# LightTable_Borders_CurrentMirror.net
KiCad netlist of a schematic drawn in EAGLE
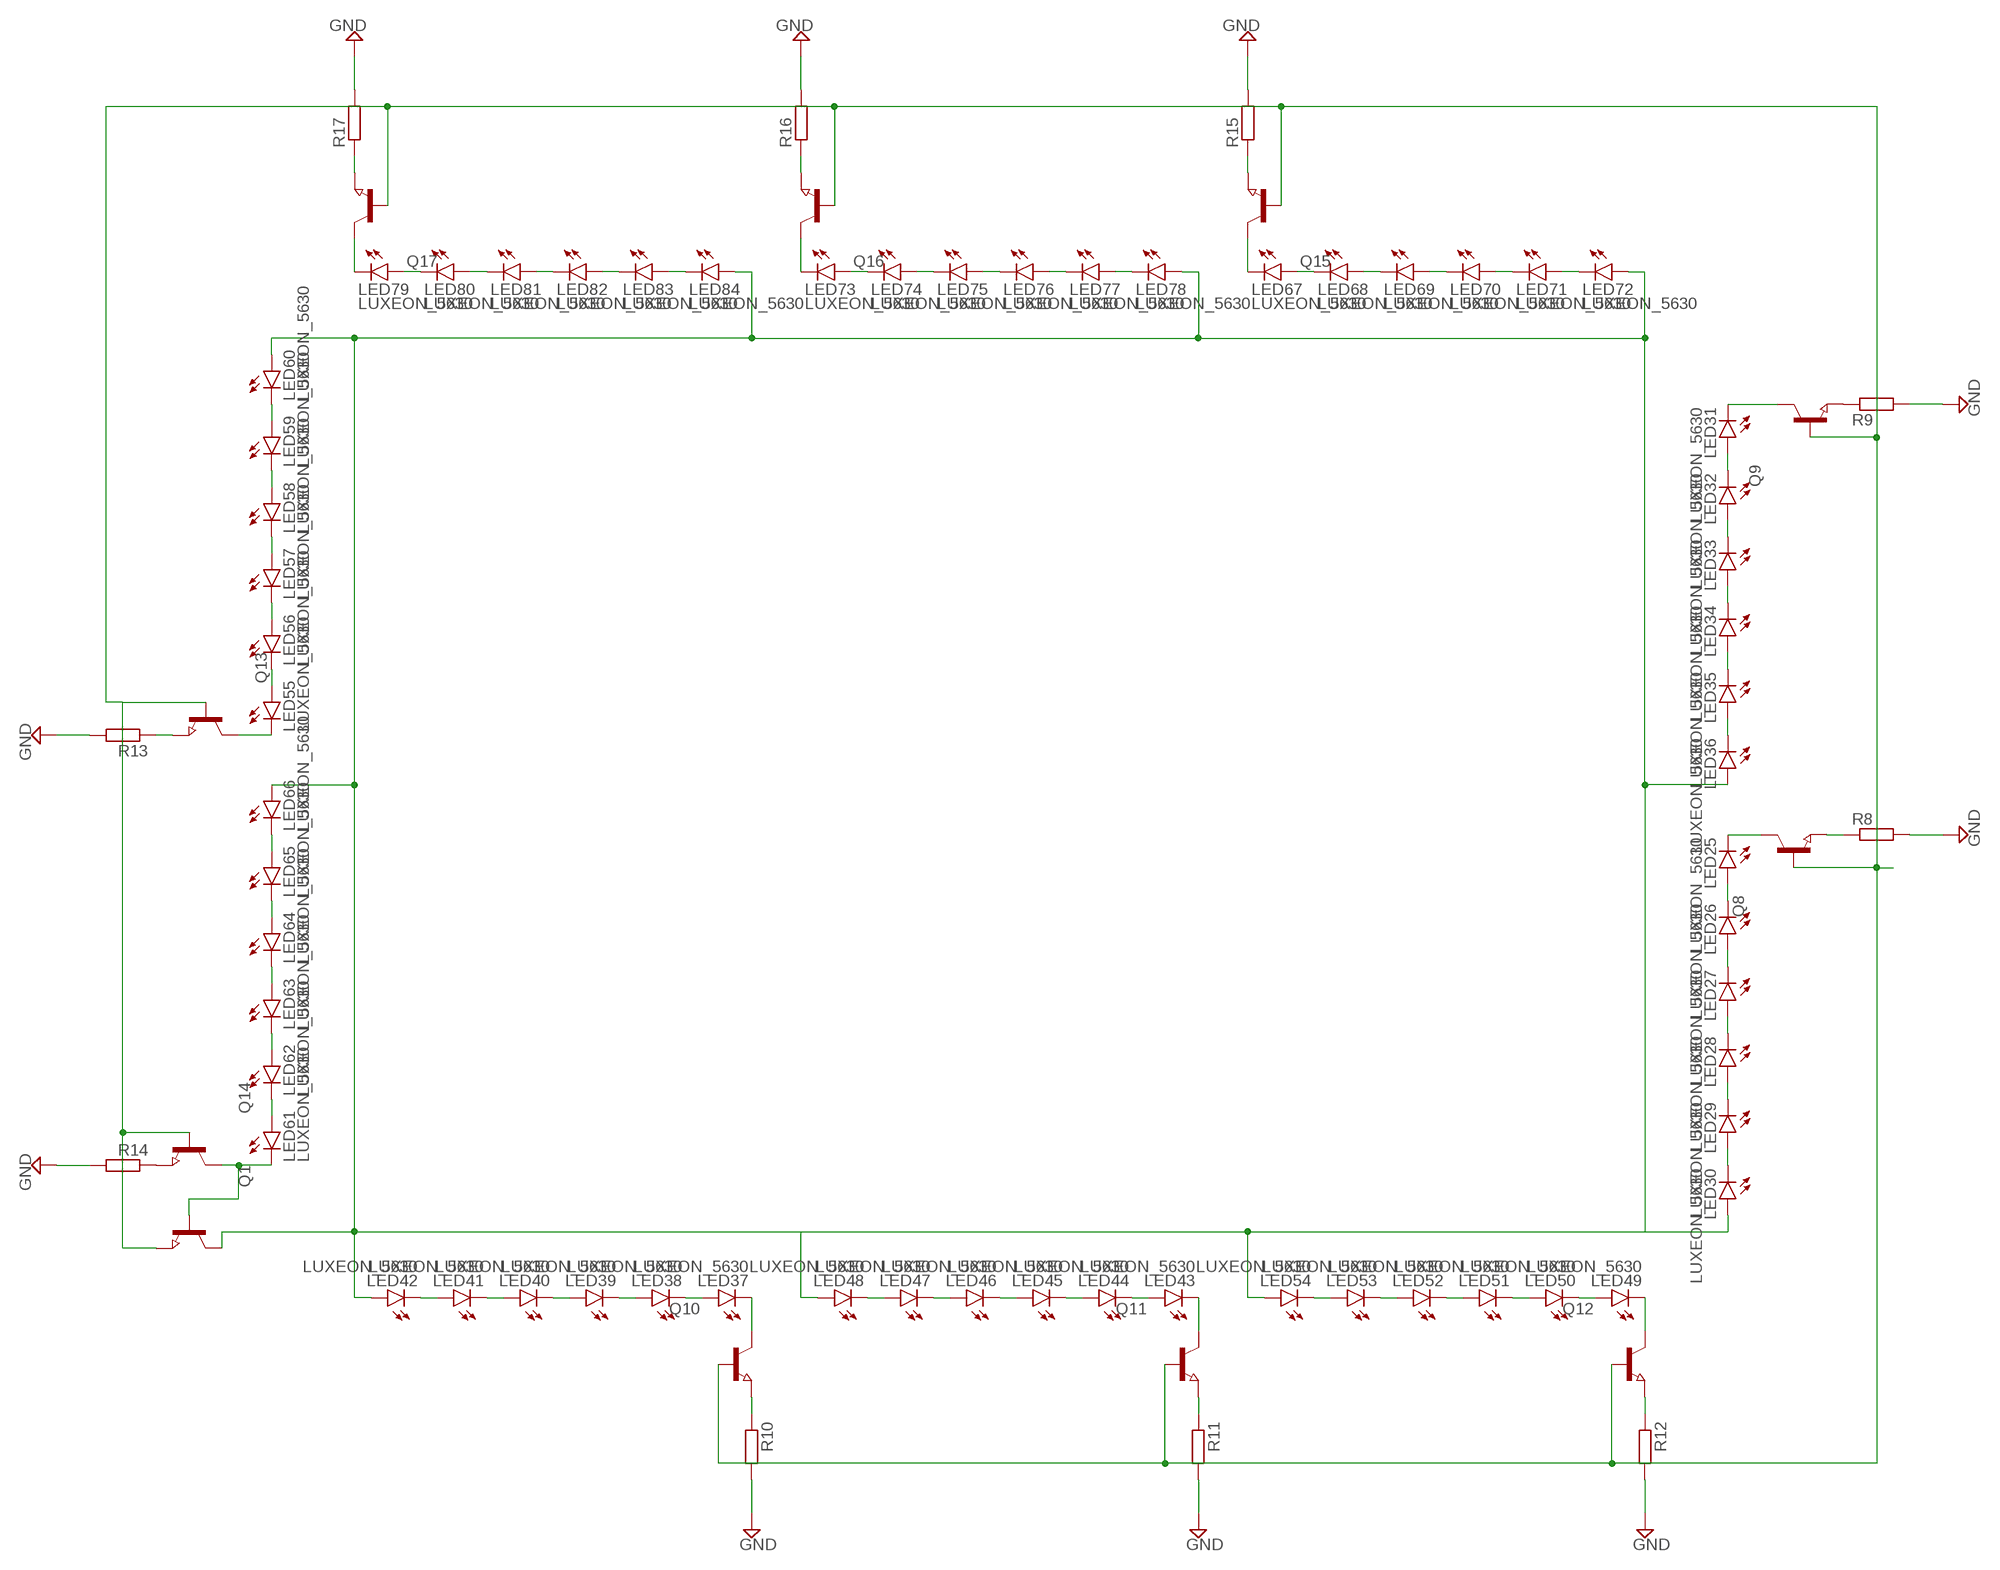
[diagram p0: schematic, sheet 1]

(export (version "E")
  (design (tool "Eeschema 10.0.6"))
  (components
    (comp (ref "LED25")
      (value "LUXEON_5630")
      (footprint "eagle-import:LUXEON_5630")
      (libsource (lib "eagle-import") (part "LUXEON_5630"))
    )
    (comp (ref "LED26")
      (value "LUXEON_5630")
      (footprint "eagle-import:LUXEON_5630")
      (libsource (lib "eagle-import") (part "LUXEON_5630"))
    )
    (comp (ref "LED27")
      (value "LUXEON_5630")
      (footprint "eagle-import:LUXEON_5630")
      (libsource (lib "eagle-import") (part "LUXEON_5630"))
    )
    (comp (ref "LED28")
      (value "LUXEON_5630")
      (footprint "eagle-import:LUXEON_5630")
      (libsource (lib "eagle-import") (part "LUXEON_5630"))
    )
    (comp (ref "LED29")
      (value "LUXEON_5630")
      (footprint "eagle-import:LUXEON_5630")
      (libsource (lib "eagle-import") (part "LUXEON_5630"))
    )
    (comp (ref "LED30")
      (value "LUXEON_5630")
      (footprint "eagle-import:LUXEON_5630")
      (libsource (lib "eagle-import") (part "LUXEON_5630"))
    )
    (comp (ref "LED31")
      (value "LUXEON_5630")
      (footprint "eagle-import:LUXEON_5630")
      (libsource (lib "eagle-import") (part "LUXEON_5630"))
    )
    (comp (ref "LED32")
      (value "LUXEON_5630")
      (footprint "eagle-import:LUXEON_5630")
      (libsource (lib "eagle-import") (part "LUXEON_5630"))
    )
    (comp (ref "LED33")
      (value "LUXEON_5630")
      (footprint "eagle-import:LUXEON_5630")
      (libsource (lib "eagle-import") (part "LUXEON_5630"))
    )
    (comp (ref "LED34")
      (value "LUXEON_5630")
      (footprint "eagle-import:LUXEON_5630")
      (libsource (lib "eagle-import") (part "LUXEON_5630"))
    )
    (comp (ref "LED35")
      (value "LUXEON_5630")
      (footprint "eagle-import:LUXEON_5630")
      (libsource (lib "eagle-import") (part "LUXEON_5630"))
    )
    (comp (ref "LED36")
      (value "LUXEON_5630")
      (footprint "eagle-import:LUXEON_5630")
      (libsource (lib "eagle-import") (part "LUXEON_5630"))
    )
    (comp (ref "LED37")
      (value "LUXEON_5630")
      (footprint "eagle-import:LUXEON_5630")
      (libsource (lib "eagle-import") (part "LUXEON_5630"))
    )
    (comp (ref "LED38")
      (value "LUXEON_5630")
      (footprint "eagle-import:LUXEON_5630")
      (libsource (lib "eagle-import") (part "LUXEON_5630"))
    )
    (comp (ref "LED39")
      (value "LUXEON_5630")
      (footprint "eagle-import:LUXEON_5630")
      (libsource (lib "eagle-import") (part "LUXEON_5630"))
    )
    (comp (ref "LED40")
      (value "LUXEON_5630")
      (footprint "eagle-import:LUXEON_5630")
      (libsource (lib "eagle-import") (part "LUXEON_5630"))
    )
    (comp (ref "LED41")
      (value "LUXEON_5630")
      (footprint "eagle-import:LUXEON_5630")
      (libsource (lib "eagle-import") (part "LUXEON_5630"))
    )
    (comp (ref "LED42")
      (value "LUXEON_5630")
      (footprint "eagle-import:LUXEON_5630")
      (libsource (lib "eagle-import") (part "LUXEON_5630"))
    )
    (comp (ref "LED43")
      (value "LUXEON_5630")
      (footprint "eagle-import:LUXEON_5630")
      (libsource (lib "eagle-import") (part "LUXEON_5630"))
    )
    (comp (ref "LED44")
      (value "LUXEON_5630")
      (footprint "eagle-import:LUXEON_5630")
      (libsource (lib "eagle-import") (part "LUXEON_5630"))
    )
    (comp (ref "LED45")
      (value "LUXEON_5630")
      (footprint "eagle-import:LUXEON_5630")
      (libsource (lib "eagle-import") (part "LUXEON_5630"))
    )
    (comp (ref "LED46")
      (value "LUXEON_5630")
      (footprint "eagle-import:LUXEON_5630")
      (libsource (lib "eagle-import") (part "LUXEON_5630"))
    )
    (comp (ref "LED47")
      (value "LUXEON_5630")
      (footprint "eagle-import:LUXEON_5630")
      (libsource (lib "eagle-import") (part "LUXEON_5630"))
    )
    (comp (ref "LED48")
      (value "LUXEON_5630")
      (footprint "eagle-import:LUXEON_5630")
      (libsource (lib "eagle-import") (part "LUXEON_5630"))
    )
    (comp (ref "LED49")
      (value "LUXEON_5630")
      (footprint "eagle-import:LUXEON_5630")
      (libsource (lib "eagle-import") (part "LUXEON_5630"))
    )
    (comp (ref "LED50")
      (value "LUXEON_5630")
      (footprint "eagle-import:LUXEON_5630")
      (libsource (lib "eagle-import") (part "LUXEON_5630"))
    )
    (comp (ref "LED51")
      (value "LUXEON_5630")
      (footprint "eagle-import:LUXEON_5630")
      (libsource (lib "eagle-import") (part "LUXEON_5630"))
    )
    (comp (ref "LED52")
      (value "LUXEON_5630")
      (footprint "eagle-import:LUXEON_5630")
      (libsource (lib "eagle-import") (part "LUXEON_5630"))
    )
    (comp (ref "LED53")
      (value "LUXEON_5630")
      (footprint "eagle-import:LUXEON_5630")
      (libsource (lib "eagle-import") (part "LUXEON_5630"))
    )
    (comp (ref "LED54")
      (value "LUXEON_5630")
      (footprint "eagle-import:LUXEON_5630")
      (libsource (lib "eagle-import") (part "LUXEON_5630"))
    )
    (comp (ref "LED55")
      (value "LUXEON_5630")
      (footprint "eagle-import:LUXEON_5630")
      (libsource (lib "eagle-import") (part "LUXEON_5630"))
    )
    (comp (ref "LED56")
      (value "LUXEON_5630")
      (footprint "eagle-import:LUXEON_5630")
      (libsource (lib "eagle-import") (part "LUXEON_5630"))
    )
    (comp (ref "LED57")
      (value "LUXEON_5630")
      (footprint "eagle-import:LUXEON_5630")
      (libsource (lib "eagle-import") (part "LUXEON_5630"))
    )
    (comp (ref "LED58")
      (value "LUXEON_5630")
      (footprint "eagle-import:LUXEON_5630")
      (libsource (lib "eagle-import") (part "LUXEON_5630"))
    )
    (comp (ref "LED59")
      (value "LUXEON_5630")
      (footprint "eagle-import:LUXEON_5630")
      (libsource (lib "eagle-import") (part "LUXEON_5630"))
    )
    (comp (ref "LED60")
      (value "LUXEON_5630")
      (footprint "eagle-import:LUXEON_5630")
      (libsource (lib "eagle-import") (part "LUXEON_5630"))
    )
    (comp (ref "LED61")
      (value "LUXEON_5630")
      (footprint "eagle-import:LUXEON_5630")
      (libsource (lib "eagle-import") (part "LUXEON_5630"))
    )
    (comp (ref "LED62")
      (value "LUXEON_5630")
      (footprint "eagle-import:LUXEON_5630")
      (libsource (lib "eagle-import") (part "LUXEON_5630"))
    )
    (comp (ref "LED63")
      (value "LUXEON_5630")
      (footprint "eagle-import:LUXEON_5630")
      (libsource (lib "eagle-import") (part "LUXEON_5630"))
    )
    (comp (ref "LED64")
      (value "LUXEON_5630")
      (footprint "eagle-import:LUXEON_5630")
      (libsource (lib "eagle-import") (part "LUXEON_5630"))
    )
    (comp (ref "LED65")
      (value "LUXEON_5630")
      (footprint "eagle-import:LUXEON_5630")
      (libsource (lib "eagle-import") (part "LUXEON_5630"))
    )
    (comp (ref "LED66")
      (value "LUXEON_5630")
      (footprint "eagle-import:LUXEON_5630")
      (libsource (lib "eagle-import") (part "LUXEON_5630"))
    )
    (comp (ref "LED67")
      (value "LUXEON_5630")
      (footprint "eagle-import:LUXEON_5630")
      (libsource (lib "eagle-import") (part "LUXEON_5630"))
    )
    (comp (ref "LED68")
      (value "LUXEON_5630")
      (footprint "eagle-import:LUXEON_5630")
      (libsource (lib "eagle-import") (part "LUXEON_5630"))
    )
    (comp (ref "LED69")
      (value "LUXEON_5630")
      (footprint "eagle-import:LUXEON_5630")
      (libsource (lib "eagle-import") (part "LUXEON_5630"))
    )
    (comp (ref "LED70")
      (value "LUXEON_5630")
      (footprint "eagle-import:LUXEON_5630")
      (libsource (lib "eagle-import") (part "LUXEON_5630"))
    )
    (comp (ref "LED71")
      (value "LUXEON_5630")
      (footprint "eagle-import:LUXEON_5630")
      (libsource (lib "eagle-import") (part "LUXEON_5630"))
    )
    (comp (ref "LED72")
      (value "LUXEON_5630")
      (footprint "eagle-import:LUXEON_5630")
      (libsource (lib "eagle-import") (part "LUXEON_5630"))
    )
    (comp (ref "LED73")
      (value "LUXEON_5630")
      (footprint "eagle-import:LUXEON_5630")
      (libsource (lib "eagle-import") (part "LUXEON_5630"))
    )
    (comp (ref "LED74")
      (value "LUXEON_5630")
      (footprint "eagle-import:LUXEON_5630")
      (libsource (lib "eagle-import") (part "LUXEON_5630"))
    )
    (comp (ref "LED75")
      (value "LUXEON_5630")
      (footprint "eagle-import:LUXEON_5630")
      (libsource (lib "eagle-import") (part "LUXEON_5630"))
    )
    (comp (ref "LED76")
      (value "LUXEON_5630")
      (footprint "eagle-import:LUXEON_5630")
      (libsource (lib "eagle-import") (part "LUXEON_5630"))
    )
    (comp (ref "LED77")
      (value "LUXEON_5630")
      (footprint "eagle-import:LUXEON_5630")
      (libsource (lib "eagle-import") (part "LUXEON_5630"))
    )
    (comp (ref "LED78")
      (value "LUXEON_5630")
      (footprint "eagle-import:LUXEON_5630")
      (libsource (lib "eagle-import") (part "LUXEON_5630"))
    )
    (comp (ref "LED79")
      (value "LUXEON_5630")
      (footprint "eagle-import:LUXEON_5630")
      (libsource (lib "eagle-import") (part "LUXEON_5630"))
    )
    (comp (ref "LED80")
      (value "LUXEON_5630")
      (footprint "eagle-import:LUXEON_5630")
      (libsource (lib "eagle-import") (part "LUXEON_5630"))
    )
    (comp (ref "LED81")
      (value "LUXEON_5630")
      (footprint "eagle-import:LUXEON_5630")
      (libsource (lib "eagle-import") (part "LUXEON_5630"))
    )
    (comp (ref "LED82")
      (value "LUXEON_5630")
      (footprint "eagle-import:LUXEON_5630")
      (libsource (lib "eagle-import") (part "LUXEON_5630"))
    )
    (comp (ref "LED83")
      (value "LUXEON_5630")
      (footprint "eagle-import:LUXEON_5630")
      (libsource (lib "eagle-import") (part "LUXEON_5630"))
    )
    (comp (ref "LED84")
      (value "LUXEON_5630")
      (footprint "eagle-import:LUXEON_5630")
      (libsource (lib "eagle-import") (part "LUXEON_5630"))
    )
    (comp (ref "Q1")
      (value "NPN-TRANSISTOR_SOT23")
      (footprint "eagle-import:SOT23")
      (libsource (lib "eagle-import") (part "NPN-TRANSISTOR_SOT23"))
    )
    (comp (ref "Q8")
      (value "NPN-TRANSISTOR_SOT23")
      (footprint "eagle-import:SOT23")
      (libsource (lib "eagle-import") (part "NPN-TRANSISTOR_SOT23"))
    )
    (comp (ref "Q9")
      (value "NPN-TRANSISTOR_SOT23")
      (footprint "eagle-import:SOT23")
      (libsource (lib "eagle-import") (part "NPN-TRANSISTOR_SOT23"))
    )
    (comp (ref "Q10")
      (value "NPN-TRANSISTOR_SOT23")
      (footprint "eagle-import:SOT23")
      (libsource (lib "eagle-import") (part "NPN-TRANSISTOR_SOT23"))
    )
    (comp (ref "Q11")
      (value "NPN-TRANSISTOR_SOT23")
      (footprint "eagle-import:SOT23")
      (libsource (lib "eagle-import") (part "NPN-TRANSISTOR_SOT23"))
    )
    (comp (ref "Q12")
      (value "NPN-TRANSISTOR_SOT23")
      (footprint "eagle-import:SOT23")
      (libsource (lib "eagle-import") (part "NPN-TRANSISTOR_SOT23"))
    )
    (comp (ref "Q13")
      (value "NPN-TRANSISTOR_SOT23")
      (footprint "eagle-import:SOT23")
      (libsource (lib "eagle-import") (part "NPN-TRANSISTOR_SOT23"))
    )
    (comp (ref "Q14")
      (value "NPN-TRANSISTOR_SOT23")
      (footprint "eagle-import:SOT23")
      (libsource (lib "eagle-import") (part "NPN-TRANSISTOR_SOT23"))
    )
    (comp (ref "Q15")
      (value "NPN-TRANSISTOR_SOT23")
      (footprint "eagle-import:SOT23")
      (libsource (lib "eagle-import") (part "NPN-TRANSISTOR_SOT23"))
    )
    (comp (ref "Q16")
      (value "NPN-TRANSISTOR_SOT23")
      (footprint "eagle-import:SOT23")
      (libsource (lib "eagle-import") (part "NPN-TRANSISTOR_SOT23"))
    )
    (comp (ref "Q17")
      (value "NPN-TRANSISTOR_SOT23")
      (footprint "eagle-import:SOT23")
      (libsource (lib "eagle-import") (part "NPN-TRANSISTOR_SOT23"))
    )
    (comp (ref "R8")
      (value "R-EU_R0805")
      (footprint "eagle-import:R0805")
      (libsource (lib "eagle-import") (part "R-EU_R0805"))
    )
    (comp (ref "R9")
      (value "R-EU_R0805")
      (footprint "eagle-import:R0805")
      (libsource (lib "eagle-import") (part "R-EU_R0805"))
    )
    (comp (ref "R10")
      (value "R-EU_R0805")
      (footprint "eagle-import:R0805")
      (libsource (lib "eagle-import") (part "R-EU_R0805"))
    )
    (comp (ref "R11")
      (value "R-EU_R0805")
      (footprint "eagle-import:R0805")
      (libsource (lib "eagle-import") (part "R-EU_R0805"))
    )
    (comp (ref "R12")
      (value "R-EU_R0805")
      (footprint "eagle-import:R0805")
      (libsource (lib "eagle-import") (part "R-EU_R0805"))
    )
    (comp (ref "R13")
      (value "R-EU_R0805")
      (footprint "eagle-import:R0805")
      (libsource (lib "eagle-import") (part "R-EU_R0805"))
    )
    (comp (ref "R14")
      (value "R-EU_R0805")
      (footprint "eagle-import:R0805")
      (libsource (lib "eagle-import") (part "R-EU_R0805"))
    )
    (comp (ref "R15")
      (value "R-EU_R0805")
      (footprint "eagle-import:R0805")
      (libsource (lib "eagle-import") (part "R-EU_R0805"))
    )
    (comp (ref "R16")
      (value "R-EU_R0805")
      (footprint "eagle-import:R0805")
      (libsource (lib "eagle-import") (part "R-EU_R0805"))
    )
    (comp (ref "R17")
      (value "R-EU_R0805")
      (footprint "eagle-import:R0805")
      (libsource (lib "eagle-import") (part "R-EU_R0805"))
    )
  )
  (nets
    (net (code "1") (name "GND") (class "Default")
      (node (ref "R10") (pin "2") (pinfunction "2_2") (pintype "passive"))
      (node (ref "R11") (pin "2") (pinfunction "2_2") (pintype "passive"))
      (node (ref "R12") (pin "2") (pinfunction "2_2") (pintype "passive"))
      (node (ref "R13") (pin "2") (pinfunction "2_2") (pintype "passive"))
      (node (ref "R14") (pin "2") (pinfunction "2_2") (pintype "passive"))
      (node (ref "R15") (pin "2") (pinfunction "2_2") (pintype "passive"))
      (node (ref "R16") (pin "2") (pinfunction "2_2") (pintype "passive"))
      (node (ref "R17") (pin "2") (pinfunction "2_2") (pintype "passive"))
      (node (ref "R8") (pin "2") (pinfunction "2_2") (pintype "passive"))
      (node (ref "R9") (pin "2") (pinfunction "2_2") (pintype "passive"))
    )
    (net (code "2") (name "Net-(LED25-A)") (class "Default")
      (node (ref "LED25") (pin "2") (pinfunction "A_2") (pintype "passive"))
      (node (ref "LED26") (pin "1@1") (pinfunction "C_1@1") (pintype "passive"))
      (node (ref "LED26") (pin "1@2") (pinfunction "C_1@2") (pintype "passive"))
    )
    (net (code "3") (name "Net-(LED26-A)") (class "Default")
      (node (ref "LED26") (pin "2") (pinfunction "A_2") (pintype "passive"))
      (node (ref "LED27") (pin "1@1") (pinfunction "C_1@1") (pintype "passive"))
      (node (ref "LED27") (pin "1@2") (pinfunction "C_1@2") (pintype "passive"))
    )
    (net (code "4") (name "Net-(LED27-A)") (class "Default")
      (node (ref "LED27") (pin "2") (pinfunction "A_2") (pintype "passive"))
      (node (ref "LED28") (pin "1@1") (pinfunction "C_1@1") (pintype "passive"))
      (node (ref "LED28") (pin "1@2") (pinfunction "C_1@2") (pintype "passive"))
    )
    (net (code "5") (name "Net-(LED28-A)") (class "Default")
      (node (ref "LED28") (pin "2") (pinfunction "A_2") (pintype "passive"))
      (node (ref "LED29") (pin "1@1") (pinfunction "C_1@1") (pintype "passive"))
      (node (ref "LED29") (pin "1@2") (pinfunction "C_1@2") (pintype "passive"))
    )
    (net (code "6") (name "Net-(LED29-A)") (class "Default")
      (node (ref "LED29") (pin "2") (pinfunction "A_2") (pintype "passive"))
      (node (ref "LED30") (pin "1@1") (pinfunction "C_1@1") (pintype "passive"))
      (node (ref "LED30") (pin "1@2") (pinfunction "C_1@2") (pintype "passive"))
    )
    (net (code "7") (name "Net-(LED30-A)") (class "Default")
      (node (ref "LED30") (pin "2") (pinfunction "A_2") (pintype "passive"))
      (node (ref "LED36") (pin "2") (pinfunction "A_2") (pintype "passive"))
      (node (ref "LED42") (pin "2") (pinfunction "A_2") (pintype "passive"))
      (node (ref "LED48") (pin "2") (pinfunction "A_2") (pintype "passive"))
      (node (ref "LED54") (pin "2") (pinfunction "A_2") (pintype "passive"))
      (node (ref "LED60") (pin "2") (pinfunction "A_2") (pintype "passive"))
      (node (ref "LED66") (pin "2") (pinfunction "A_2") (pintype "passive"))
      (node (ref "LED72") (pin "2") (pinfunction "A_2") (pintype "passive"))
      (node (ref "LED78") (pin "2") (pinfunction "A_2") (pintype "passive"))
      (node (ref "LED84") (pin "2") (pinfunction "A_2") (pintype "passive"))
      (node (ref "Q1") (pin "3") (pinfunction "C_3") (pintype "passive"))
    )
    (net (code "8") (name "Net-(LED31-A)") (class "Default")
      (node (ref "LED31") (pin "2") (pinfunction "A_2") (pintype "passive"))
      (node (ref "LED32") (pin "1@1") (pinfunction "C_1@1") (pintype "passive"))
      (node (ref "LED32") (pin "1@2") (pinfunction "C_1@2") (pintype "passive"))
    )
    (net (code "9") (name "Net-(LED32-A)") (class "Default")
      (node (ref "LED32") (pin "2") (pinfunction "A_2") (pintype "passive"))
      (node (ref "LED33") (pin "1@1") (pinfunction "C_1@1") (pintype "passive"))
      (node (ref "LED33") (pin "1@2") (pinfunction "C_1@2") (pintype "passive"))
    )
    (net (code "10") (name "Net-(LED33-A)") (class "Default")
      (node (ref "LED33") (pin "2") (pinfunction "A_2") (pintype "passive"))
      (node (ref "LED34") (pin "1@1") (pinfunction "C_1@1") (pintype "passive"))
      (node (ref "LED34") (pin "1@2") (pinfunction "C_1@2") (pintype "passive"))
    )
    (net (code "11") (name "Net-(LED34-A)") (class "Default")
      (node (ref "LED34") (pin "2") (pinfunction "A_2") (pintype "passive"))
      (node (ref "LED35") (pin "1@1") (pinfunction "C_1@1") (pintype "passive"))
      (node (ref "LED35") (pin "1@2") (pinfunction "C_1@2") (pintype "passive"))
    )
    (net (code "12") (name "Net-(LED35-A)") (class "Default")
      (node (ref "LED35") (pin "2") (pinfunction "A_2") (pintype "passive"))
      (node (ref "LED36") (pin "1@1") (pinfunction "C_1@1") (pintype "passive"))
      (node (ref "LED36") (pin "1@2") (pinfunction "C_1@2") (pintype "passive"))
    )
    (net (code "13") (name "Net-(LED37-A)") (class "Default")
      (node (ref "LED37") (pin "2") (pinfunction "A_2") (pintype "passive"))
      (node (ref "LED38") (pin "1@1") (pinfunction "C_1@1") (pintype "passive"))
      (node (ref "LED38") (pin "1@2") (pinfunction "C_1@2") (pintype "passive"))
    )
    (net (code "14") (name "Net-(LED38-A)") (class "Default")
      (node (ref "LED38") (pin "2") (pinfunction "A_2") (pintype "passive"))
      (node (ref "LED39") (pin "1@1") (pinfunction "C_1@1") (pintype "passive"))
      (node (ref "LED39") (pin "1@2") (pinfunction "C_1@2") (pintype "passive"))
    )
    (net (code "15") (name "Net-(LED39-A)") (class "Default")
      (node (ref "LED39") (pin "2") (pinfunction "A_2") (pintype "passive"))
      (node (ref "LED40") (pin "1@1") (pinfunction "C_1@1") (pintype "passive"))
      (node (ref "LED40") (pin "1@2") (pinfunction "C_1@2") (pintype "passive"))
    )
    (net (code "16") (name "Net-(LED40-A)") (class "Default")
      (node (ref "LED40") (pin "2") (pinfunction "A_2") (pintype "passive"))
      (node (ref "LED41") (pin "1@1") (pinfunction "C_1@1") (pintype "passive"))
      (node (ref "LED41") (pin "1@2") (pinfunction "C_1@2") (pintype "passive"))
    )
    (net (code "17") (name "Net-(LED41-A)") (class "Default")
      (node (ref "LED41") (pin "2") (pinfunction "A_2") (pintype "passive"))
      (node (ref "LED42") (pin "1@1") (pinfunction "C_1@1") (pintype "passive"))
      (node (ref "LED42") (pin "1@2") (pinfunction "C_1@2") (pintype "passive"))
    )
    (net (code "18") (name "Net-(LED43-A)") (class "Default")
      (node (ref "LED43") (pin "2") (pinfunction "A_2") (pintype "passive"))
      (node (ref "LED44") (pin "1@1") (pinfunction "C_1@1") (pintype "passive"))
      (node (ref "LED44") (pin "1@2") (pinfunction "C_1@2") (pintype "passive"))
    )
    (net (code "19") (name "Net-(LED44-A)") (class "Default")
      (node (ref "LED44") (pin "2") (pinfunction "A_2") (pintype "passive"))
      (node (ref "LED45") (pin "1@1") (pinfunction "C_1@1") (pintype "passive"))
      (node (ref "LED45") (pin "1@2") (pinfunction "C_1@2") (pintype "passive"))
    )
    (net (code "20") (name "Net-(LED45-A)") (class "Default")
      (node (ref "LED45") (pin "2") (pinfunction "A_2") (pintype "passive"))
      (node (ref "LED46") (pin "1@1") (pinfunction "C_1@1") (pintype "passive"))
      (node (ref "LED46") (pin "1@2") (pinfunction "C_1@2") (pintype "passive"))
    )
    (net (code "21") (name "Net-(LED46-A)") (class "Default")
      (node (ref "LED46") (pin "2") (pinfunction "A_2") (pintype "passive"))
      (node (ref "LED47") (pin "1@1") (pinfunction "C_1@1") (pintype "passive"))
      (node (ref "LED47") (pin "1@2") (pinfunction "C_1@2") (pintype "passive"))
    )
    (net (code "22") (name "Net-(LED47-A)") (class "Default")
      (node (ref "LED47") (pin "2") (pinfunction "A_2") (pintype "passive"))
      (node (ref "LED48") (pin "1@1") (pinfunction "C_1@1") (pintype "passive"))
      (node (ref "LED48") (pin "1@2") (pinfunction "C_1@2") (pintype "passive"))
    )
    (net (code "23") (name "Net-(LED49-A)") (class "Default")
      (node (ref "LED49") (pin "2") (pinfunction "A_2") (pintype "passive"))
      (node (ref "LED50") (pin "1@1") (pinfunction "C_1@1") (pintype "passive"))
      (node (ref "LED50") (pin "1@2") (pinfunction "C_1@2") (pintype "passive"))
    )
    (net (code "24") (name "Net-(LED50-A)") (class "Default")
      (node (ref "LED50") (pin "2") (pinfunction "A_2") (pintype "passive"))
      (node (ref "LED51") (pin "1@1") (pinfunction "C_1@1") (pintype "passive"))
      (node (ref "LED51") (pin "1@2") (pinfunction "C_1@2") (pintype "passive"))
    )
    (net (code "25") (name "Net-(LED51-A)") (class "Default")
      (node (ref "LED51") (pin "2") (pinfunction "A_2") (pintype "passive"))
      (node (ref "LED52") (pin "1@1") (pinfunction "C_1@1") (pintype "passive"))
      (node (ref "LED52") (pin "1@2") (pinfunction "C_1@2") (pintype "passive"))
    )
    (net (code "26") (name "Net-(LED52-A)") (class "Default")
      (node (ref "LED52") (pin "2") (pinfunction "A_2") (pintype "passive"))
      (node (ref "LED53") (pin "1@1") (pinfunction "C_1@1") (pintype "passive"))
      (node (ref "LED53") (pin "1@2") (pinfunction "C_1@2") (pintype "passive"))
    )
    (net (code "27") (name "Net-(LED53-A)") (class "Default")
      (node (ref "LED53") (pin "2") (pinfunction "A_2") (pintype "passive"))
      (node (ref "LED54") (pin "1@1") (pinfunction "C_1@1") (pintype "passive"))
      (node (ref "LED54") (pin "1@2") (pinfunction "C_1@2") (pintype "passive"))
    )
    (net (code "28") (name "Net-(LED55-A)") (class "Default")
      (node (ref "LED55") (pin "2") (pinfunction "A_2") (pintype "passive"))
      (node (ref "LED56") (pin "1@1") (pinfunction "C_1@1") (pintype "passive"))
      (node (ref "LED56") (pin "1@2") (pinfunction "C_1@2") (pintype "passive"))
    )
    (net (code "29") (name "Net-(LED56-A)") (class "Default")
      (node (ref "LED56") (pin "2") (pinfunction "A_2") (pintype "passive"))
      (node (ref "LED57") (pin "1@1") (pinfunction "C_1@1") (pintype "passive"))
      (node (ref "LED57") (pin "1@2") (pinfunction "C_1@2") (pintype "passive"))
    )
    (net (code "30") (name "Net-(LED57-A)") (class "Default")
      (node (ref "LED57") (pin "2") (pinfunction "A_2") (pintype "passive"))
      (node (ref "LED58") (pin "1@1") (pinfunction "C_1@1") (pintype "passive"))
      (node (ref "LED58") (pin "1@2") (pinfunction "C_1@2") (pintype "passive"))
    )
    (net (code "31") (name "Net-(LED58-A)") (class "Default")
      (node (ref "LED58") (pin "2") (pinfunction "A_2") (pintype "passive"))
      (node (ref "LED59") (pin "1@1") (pinfunction "C_1@1") (pintype "passive"))
      (node (ref "LED59") (pin "1@2") (pinfunction "C_1@2") (pintype "passive"))
    )
    (net (code "32") (name "Net-(LED59-A)") (class "Default")
      (node (ref "LED59") (pin "2") (pinfunction "A_2") (pintype "passive"))
      (node (ref "LED60") (pin "1@1") (pinfunction "C_1@1") (pintype "passive"))
      (node (ref "LED60") (pin "1@2") (pinfunction "C_1@2") (pintype "passive"))
    )
    (net (code "33") (name "Net-(LED61-A)") (class "Default")
      (node (ref "LED61") (pin "2") (pinfunction "A_2") (pintype "passive"))
      (node (ref "LED62") (pin "1@1") (pinfunction "C_1@1") (pintype "passive"))
      (node (ref "LED62") (pin "1@2") (pinfunction "C_1@2") (pintype "passive"))
    )
    (net (code "34") (name "Net-(LED62-A)") (class "Default")
      (node (ref "LED62") (pin "2") (pinfunction "A_2") (pintype "passive"))
      (node (ref "LED63") (pin "1@1") (pinfunction "C_1@1") (pintype "passive"))
      (node (ref "LED63") (pin "1@2") (pinfunction "C_1@2") (pintype "passive"))
    )
    (net (code "35") (name "Net-(LED63-A)") (class "Default")
      (node (ref "LED63") (pin "2") (pinfunction "A_2") (pintype "passive"))
      (node (ref "LED64") (pin "1@1") (pinfunction "C_1@1") (pintype "passive"))
      (node (ref "LED64") (pin "1@2") (pinfunction "C_1@2") (pintype "passive"))
    )
    (net (code "36") (name "Net-(LED64-A)") (class "Default")
      (node (ref "LED64") (pin "2") (pinfunction "A_2") (pintype "passive"))
      (node (ref "LED65") (pin "1@1") (pinfunction "C_1@1") (pintype "passive"))
      (node (ref "LED65") (pin "1@2") (pinfunction "C_1@2") (pintype "passive"))
    )
    (net (code "37") (name "Net-(LED65-A)") (class "Default")
      (node (ref "LED65") (pin "2") (pinfunction "A_2") (pintype "passive"))
      (node (ref "LED66") (pin "1@1") (pinfunction "C_1@1") (pintype "passive"))
      (node (ref "LED66") (pin "1@2") (pinfunction "C_1@2") (pintype "passive"))
    )
    (net (code "38") (name "Net-(LED67-A)") (class "Default")
      (node (ref "LED67") (pin "2") (pinfunction "A_2") (pintype "passive"))
      (node (ref "LED68") (pin "1@1") (pinfunction "C_1@1") (pintype "passive"))
      (node (ref "LED68") (pin "1@2") (pinfunction "C_1@2") (pintype "passive"))
    )
    (net (code "39") (name "Net-(LED68-A)") (class "Default")
      (node (ref "LED68") (pin "2") (pinfunction "A_2") (pintype "passive"))
      (node (ref "LED69") (pin "1@1") (pinfunction "C_1@1") (pintype "passive"))
      (node (ref "LED69") (pin "1@2") (pinfunction "C_1@2") (pintype "passive"))
    )
    (net (code "40") (name "Net-(LED69-A)") (class "Default")
      (node (ref "LED69") (pin "2") (pinfunction "A_2") (pintype "passive"))
      (node (ref "LED70") (pin "1@1") (pinfunction "C_1@1") (pintype "passive"))
      (node (ref "LED70") (pin "1@2") (pinfunction "C_1@2") (pintype "passive"))
    )
    (net (code "41") (name "Net-(LED70-A)") (class "Default")
      (node (ref "LED70") (pin "2") (pinfunction "A_2") (pintype "passive"))
      (node (ref "LED71") (pin "1@1") (pinfunction "C_1@1") (pintype "passive"))
      (node (ref "LED71") (pin "1@2") (pinfunction "C_1@2") (pintype "passive"))
    )
    (net (code "42") (name "Net-(LED71-A)") (class "Default")
      (node (ref "LED71") (pin "2") (pinfunction "A_2") (pintype "passive"))
      (node (ref "LED72") (pin "1@1") (pinfunction "C_1@1") (pintype "passive"))
      (node (ref "LED72") (pin "1@2") (pinfunction "C_1@2") (pintype "passive"))
    )
    (net (code "43") (name "Net-(LED73-A)") (class "Default")
      (node (ref "LED73") (pin "2") (pinfunction "A_2") (pintype "passive"))
      (node (ref "LED74") (pin "1@1") (pinfunction "C_1@1") (pintype "passive"))
      (node (ref "LED74") (pin "1@2") (pinfunction "C_1@2") (pintype "passive"))
    )
    (net (code "44") (name "Net-(LED74-A)") (class "Default")
      (node (ref "LED74") (pin "2") (pinfunction "A_2") (pintype "passive"))
      (node (ref "LED75") (pin "1@1") (pinfunction "C_1@1") (pintype "passive"))
      (node (ref "LED75") (pin "1@2") (pinfunction "C_1@2") (pintype "passive"))
    )
    (net (code "45") (name "Net-(LED75-A)") (class "Default")
      (node (ref "LED75") (pin "2") (pinfunction "A_2") (pintype "passive"))
      (node (ref "LED76") (pin "1@1") (pinfunction "C_1@1") (pintype "passive"))
      (node (ref "LED76") (pin "1@2") (pinfunction "C_1@2") (pintype "passive"))
    )
    (net (code "46") (name "Net-(LED76-A)") (class "Default")
      (node (ref "LED76") (pin "2") (pinfunction "A_2") (pintype "passive"))
      (node (ref "LED77") (pin "1@1") (pinfunction "C_1@1") (pintype "passive"))
      (node (ref "LED77") (pin "1@2") (pinfunction "C_1@2") (pintype "passive"))
    )
    (net (code "47") (name "Net-(LED77-A)") (class "Default")
      (node (ref "LED77") (pin "2") (pinfunction "A_2") (pintype "passive"))
      (node (ref "LED78") (pin "1@1") (pinfunction "C_1@1") (pintype "passive"))
      (node (ref "LED78") (pin "1@2") (pinfunction "C_1@2") (pintype "passive"))
    )
    (net (code "48") (name "Net-(LED79-A)") (class "Default")
      (node (ref "LED79") (pin "2") (pinfunction "A_2") (pintype "passive"))
      (node (ref "LED80") (pin "1@1") (pinfunction "C_1@1") (pintype "passive"))
      (node (ref "LED80") (pin "1@2") (pinfunction "C_1@2") (pintype "passive"))
    )
    (net (code "49") (name "Net-(LED80-A)") (class "Default")
      (node (ref "LED80") (pin "2") (pinfunction "A_2") (pintype "passive"))
      (node (ref "LED81") (pin "1@1") (pinfunction "C_1@1") (pintype "passive"))
      (node (ref "LED81") (pin "1@2") (pinfunction "C_1@2") (pintype "passive"))
    )
    (net (code "50") (name "Net-(LED81-A)") (class "Default")
      (node (ref "LED81") (pin "2") (pinfunction "A_2") (pintype "passive"))
      (node (ref "LED82") (pin "1@1") (pinfunction "C_1@1") (pintype "passive"))
      (node (ref "LED82") (pin "1@2") (pinfunction "C_1@2") (pintype "passive"))
    )
    (net (code "51") (name "Net-(LED82-A)") (class "Default")
      (node (ref "LED82") (pin "2") (pinfunction "A_2") (pintype "passive"))
      (node (ref "LED83") (pin "1@1") (pinfunction "C_1@1") (pintype "passive"))
      (node (ref "LED83") (pin "1@2") (pinfunction "C_1@2") (pintype "passive"))
    )
    (net (code "52") (name "Net-(LED83-A)") (class "Default")
      (node (ref "LED83") (pin "2") (pinfunction "A_2") (pintype "passive"))
      (node (ref "LED84") (pin "1@1") (pinfunction "C_1@1") (pintype "passive"))
      (node (ref "LED84") (pin "1@2") (pinfunction "C_1@2") (pintype "passive"))
    )
    (net (code "53") (name "Net-(Q1-B)") (class "Default")
      (node (ref "LED61") (pin "1@1") (pinfunction "C_1@1") (pintype "passive"))
      (node (ref "LED61") (pin "1@2") (pinfunction "C_1@2") (pintype "passive"))
      (node (ref "Q1") (pin "1") (pinfunction "B_1") (pintype "passive"))
      (node (ref "Q14") (pin "3") (pinfunction "C_3") (pintype "passive"))
    )
    (net (code "54") (name "Net-(Q1-E)") (class "Default")
      (node (ref "Q1") (pin "2") (pinfunction "E_2") (pintype "passive"))
      (node (ref "Q10") (pin "1") (pinfunction "B_1") (pintype "passive"))
      (node (ref "Q11") (pin "1") (pinfunction "B_1") (pintype "passive"))
      (node (ref "Q12") (pin "1") (pinfunction "B_1") (pintype "passive"))
      (node (ref "Q13") (pin "1") (pinfunction "B_1") (pintype "passive"))
      (node (ref "Q14") (pin "1") (pinfunction "B_1") (pintype "passive"))
      (node (ref "Q15") (pin "1") (pinfunction "B_1") (pintype "passive"))
      (node (ref "Q16") (pin "1") (pinfunction "B_1") (pintype "passive"))
      (node (ref "Q17") (pin "1") (pinfunction "B_1") (pintype "passive"))
      (node (ref "Q8") (pin "1") (pinfunction "B_1") (pintype "passive"))
      (node (ref "Q9") (pin "1") (pinfunction "B_1") (pintype "passive"))
    )
    (net (code "55") (name "Net-(Q8-C)") (class "Default")
      (node (ref "LED25") (pin "1@1") (pinfunction "C_1@1") (pintype "passive"))
      (node (ref "LED25") (pin "1@2") (pinfunction "C_1@2") (pintype "passive"))
      (node (ref "Q8") (pin "3") (pinfunction "C_3") (pintype "passive"))
    )
    (net (code "56") (name "Net-(Q8-E)") (class "Default")
      (node (ref "Q8") (pin "2") (pinfunction "E_2") (pintype "passive"))
      (node (ref "R8") (pin "1") (pinfunction "1_1") (pintype "passive"))
    )
    (net (code "57") (name "Net-(Q9-C)") (class "Default")
      (node (ref "LED31") (pin "1@1") (pinfunction "C_1@1") (pintype "passive"))
      (node (ref "LED31") (pin "1@2") (pinfunction "C_1@2") (pintype "passive"))
      (node (ref "Q9") (pin "3") (pinfunction "C_3") (pintype "passive"))
    )
    (net (code "58") (name "Net-(Q9-E)") (class "Default")
      (node (ref "Q9") (pin "2") (pinfunction "E_2") (pintype "passive"))
      (node (ref "R9") (pin "1") (pinfunction "1_1") (pintype "passive"))
    )
    (net (code "59") (name "Net-(Q10-C)") (class "Default")
      (node (ref "LED37") (pin "1@1") (pinfunction "C_1@1") (pintype "passive"))
      (node (ref "LED37") (pin "1@2") (pinfunction "C_1@2") (pintype "passive"))
      (node (ref "Q10") (pin "3") (pinfunction "C_3") (pintype "passive"))
    )
    (net (code "60") (name "Net-(Q10-E)") (class "Default")
      (node (ref "Q10") (pin "2") (pinfunction "E_2") (pintype "passive"))
      (node (ref "R10") (pin "1") (pinfunction "1_1") (pintype "passive"))
    )
    (net (code "61") (name "Net-(Q11-C)") (class "Default")
      (node (ref "LED43") (pin "1@1") (pinfunction "C_1@1") (pintype "passive"))
      (node (ref "LED43") (pin "1@2") (pinfunction "C_1@2") (pintype "passive"))
      (node (ref "Q11") (pin "3") (pinfunction "C_3") (pintype "passive"))
    )
    (net (code "62") (name "Net-(Q11-E)") (class "Default")
      (node (ref "Q11") (pin "2") (pinfunction "E_2") (pintype "passive"))
      (node (ref "R11") (pin "1") (pinfunction "1_1") (pintype "passive"))
    )
    (net (code "63") (name "Net-(Q12-C)") (class "Default")
      (node (ref "LED49") (pin "1@1") (pinfunction "C_1@1") (pintype "passive"))
      (node (ref "LED49") (pin "1@2") (pinfunction "C_1@2") (pintype "passive"))
      (node (ref "Q12") (pin "3") (pinfunction "C_3") (pintype "passive"))
    )
    (net (code "64") (name "Net-(Q12-E)") (class "Default")
      (node (ref "Q12") (pin "2") (pinfunction "E_2") (pintype "passive"))
      (node (ref "R12") (pin "1") (pinfunction "1_1") (pintype "passive"))
    )
    (net (code "65") (name "Net-(Q13-C)") (class "Default")
      (node (ref "LED55") (pin "1@1") (pinfunction "C_1@1") (pintype "passive"))
      (node (ref "LED55") (pin "1@2") (pinfunction "C_1@2") (pintype "passive"))
      (node (ref "Q13") (pin "3") (pinfunction "C_3") (pintype "passive"))
    )
    (net (code "66") (name "Net-(Q13-E)") (class "Default")
      (node (ref "Q13") (pin "2") (pinfunction "E_2") (pintype "passive"))
      (node (ref "R13") (pin "1") (pinfunction "1_1") (pintype "passive"))
    )
    (net (code "67") (name "Net-(Q14-E)") (class "Default")
      (node (ref "Q14") (pin "2") (pinfunction "E_2") (pintype "passive"))
      (node (ref "R14") (pin "1") (pinfunction "1_1") (pintype "passive"))
    )
    (net (code "68") (name "Net-(Q15-C)") (class "Default")
      (node (ref "LED67") (pin "1@1") (pinfunction "C_1@1") (pintype "passive"))
      (node (ref "LED67") (pin "1@2") (pinfunction "C_1@2") (pintype "passive"))
      (node (ref "Q15") (pin "3") (pinfunction "C_3") (pintype "passive"))
    )
    (net (code "69") (name "Net-(Q15-E)") (class "Default")
      (node (ref "Q15") (pin "2") (pinfunction "E_2") (pintype "passive"))
      (node (ref "R15") (pin "1") (pinfunction "1_1") (pintype "passive"))
    )
    (net (code "70") (name "Net-(Q16-C)") (class "Default")
      (node (ref "LED73") (pin "1@1") (pinfunction "C_1@1") (pintype "passive"))
      (node (ref "LED73") (pin "1@2") (pinfunction "C_1@2") (pintype "passive"))
      (node (ref "Q16") (pin "3") (pinfunction "C_3") (pintype "passive"))
    )
    (net (code "71") (name "Net-(Q16-E)") (class "Default")
      (node (ref "Q16") (pin "2") (pinfunction "E_2") (pintype "passive"))
      (node (ref "R16") (pin "1") (pinfunction "1_1") (pintype "passive"))
    )
    (net (code "72") (name "Net-(Q17-C)") (class "Default")
      (node (ref "LED79") (pin "1@1") (pinfunction "C_1@1") (pintype "passive"))
      (node (ref "LED79") (pin "1@2") (pinfunction "C_1@2") (pintype "passive"))
      (node (ref "Q17") (pin "3") (pinfunction "C_3") (pintype "passive"))
    )
    (net (code "73") (name "Net-(Q17-E)") (class "Default")
      (node (ref "Q17") (pin "2") (pinfunction "E_2") (pintype "passive"))
      (node (ref "R17") (pin "1") (pinfunction "1_1") (pintype "passive"))
    )
  )
)
